# busyIdleDetectionStratasys.net
KiCad netlist of a schematic drawn in EAGLE
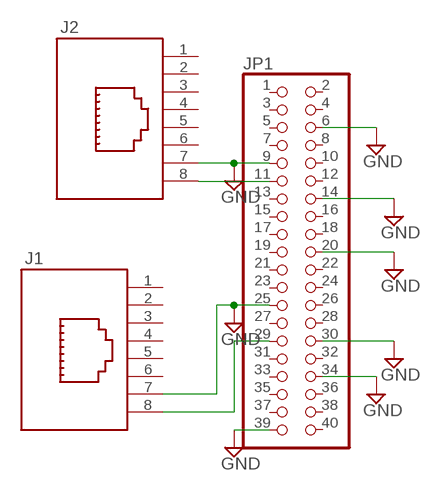
[diagram p0: schematic, sheet 1]

(export (version "E")
  (design (tool "Eeschema 10.0.6"))
  (components
    (comp (ref "J1")
      (value "634008137221")
      (footprint "eagle-import:634008137221")
      (libsource (lib "eagle-import") (part "634008137221"))
    )
    (comp (ref "J2")
      (value "634008137221")
      (footprint "eagle-import:634008137221")
      (libsource (lib "eagle-import") (part "634008137221"))
    )
    (comp (ref "JP1")
      (value "PINHD-2X20")
      (footprint "eagle-import:2X20")
      (libsource (lib "eagle-import") (part "PINHD-2X20"))
    )
  )
  (nets
    (net (code "1") (name "GND") (class "Default")
      (node (ref "J1") (pin "7") (pinfunction "2_7") (pintype "passive"))
      (node (ref "J2") (pin "7") (pinfunction "2_7") (pintype "passive"))
      (node (ref "JP1") (pin "14") (pinfunction "14_14") (pintype "passive"))
      (node (ref "JP1") (pin "20") (pinfunction "20_20") (pintype "passive"))
      (node (ref "JP1") (pin "25") (pinfunction "25_25") (pintype "passive"))
      (node (ref "JP1") (pin "30") (pinfunction "30_30") (pintype "passive"))
      (node (ref "JP1") (pin "34") (pinfunction "34_34") (pintype "passive"))
      (node (ref "JP1") (pin "39") (pinfunction "39_39") (pintype "passive"))
      (node (ref "JP1") (pin "6") (pinfunction "6_6") (pintype "passive"))
      (node (ref "JP1") (pin "9") (pinfunction "9_9") (pintype "passive"))
    )
    (net (code "2") (name "Net-(J1-1)") (class "Default")
      (node (ref "J1") (pin "8") (pinfunction "1_8") (pintype "passive"))
      (node (ref "JP1") (pin "29") (pinfunction "29_29") (pintype "passive"))
    )
    (net (code "3") (name "Net-(J2-1)") (class "Default")
      (node (ref "J2") (pin "8") (pinfunction "1_8") (pintype "passive"))
      (node (ref "JP1") (pin "11") (pinfunction "11_11") (pintype "passive"))
    )
    (net (code "4") (name "unconnected-(J1-3-Pad6)") (class "Default")
      (node (ref "J1") (pin "6") (pinfunction "3_6") (pintype "passive"))
    )
    (net (code "5") (name "unconnected-(J1-4-Pad5)") (class "Default")
      (node (ref "J1") (pin "5") (pinfunction "4_5") (pintype "passive"))
    )
    (net (code "6") (name "unconnected-(J1-5-Pad4)") (class "Default")
      (node (ref "J1") (pin "4") (pinfunction "5_4") (pintype "passive"))
    )
    (net (code "7") (name "unconnected-(J1-6-Pad3)") (class "Default")
      (node (ref "J1") (pin "3") (pinfunction "6_3") (pintype "passive"))
    )
    (net (code "8") (name "unconnected-(J1-7-Pad2)") (class "Default")
      (node (ref "J1") (pin "2") (pinfunction "7_2") (pintype "passive"))
    )
    (net (code "9") (name "unconnected-(J1-8-Pad1)") (class "Default")
      (node (ref "J1") (pin "1") (pinfunction "8_1") (pintype "passive"))
    )
    (net (code "10") (name "unconnected-(J2-3-Pad6)") (class "Default")
      (node (ref "J2") (pin "6") (pinfunction "3_6") (pintype "passive"))
    )
    (net (code "11") (name "unconnected-(J2-4-Pad5)") (class "Default")
      (node (ref "J2") (pin "5") (pinfunction "4_5") (pintype "passive"))
    )
    (net (code "12") (name "unconnected-(J2-5-Pad4)") (class "Default")
      (node (ref "J2") (pin "4") (pinfunction "5_4") (pintype "passive"))
    )
    (net (code "13") (name "unconnected-(J2-6-Pad3)") (class "Default")
      (node (ref "J2") (pin "3") (pinfunction "6_3") (pintype "passive"))
    )
    (net (code "14") (name "unconnected-(J2-7-Pad2)") (class "Default")
      (node (ref "J2") (pin "2") (pinfunction "7_2") (pintype "passive"))
    )
    (net (code "15") (name "unconnected-(J2-8-Pad1)") (class "Default")
      (node (ref "J2") (pin "1") (pinfunction "8_1") (pintype "passive"))
    )
    (net (code "16") (name "unconnected-(JP1-Pad1)") (class "Default")
      (node (ref "JP1") (pin "1") (pinfunction "1_1") (pintype "passive"))
    )
    (net (code "17") (name "unconnected-(JP1-Pad2)") (class "Default")
      (node (ref "JP1") (pin "2") (pinfunction "2_2") (pintype "passive"))
    )
    (net (code "18") (name "unconnected-(JP1-Pad3)") (class "Default")
      (node (ref "JP1") (pin "3") (pinfunction "3_3") (pintype "passive"))
    )
    (net (code "19") (name "unconnected-(JP1-Pad4)") (class "Default")
      (node (ref "JP1") (pin "4") (pinfunction "4_4") (pintype "passive"))
    )
    (net (code "20") (name "unconnected-(JP1-Pad5)") (class "Default")
      (node (ref "JP1") (pin "5") (pinfunction "5_5") (pintype "passive"))
    )
    (net (code "21") (name "unconnected-(JP1-Pad7)") (class "Default")
      (node (ref "JP1") (pin "7") (pinfunction "7_7") (pintype "passive"))
    )
    (net (code "22") (name "unconnected-(JP1-Pad8)") (class "Default")
      (node (ref "JP1") (pin "8") (pinfunction "8_8") (pintype "passive"))
    )
    (net (code "23") (name "unconnected-(JP1-Pad10)") (class "Default")
      (node (ref "JP1") (pin "10") (pinfunction "10_10") (pintype "passive"))
    )
    (net (code "24") (name "unconnected-(JP1-Pad12)") (class "Default")
      (node (ref "JP1") (pin "12") (pinfunction "12_12") (pintype "passive"))
    )
    (net (code "25") (name "unconnected-(JP1-Pad13)") (class "Default")
      (node (ref "JP1") (pin "13") (pinfunction "13_13") (pintype "passive"))
    )
    (net (code "26") (name "unconnected-(JP1-Pad15)") (class "Default")
      (node (ref "JP1") (pin "15") (pinfunction "15_15") (pintype "passive"))
    )
    (net (code "27") (name "unconnected-(JP1-Pad16)") (class "Default")
      (node (ref "JP1") (pin "16") (pinfunction "16_16") (pintype "passive"))
    )
    (net (code "28") (name "unconnected-(JP1-Pad17)") (class "Default")
      (node (ref "JP1") (pin "17") (pinfunction "17_17") (pintype "passive"))
    )
    (net (code "29") (name "unconnected-(JP1-Pad18)") (class "Default")
      (node (ref "JP1") (pin "18") (pinfunction "18_18") (pintype "passive"))
    )
    (net (code "30") (name "unconnected-(JP1-Pad19)") (class "Default")
      (node (ref "JP1") (pin "19") (pinfunction "19_19") (pintype "passive"))
    )
    (net (code "31") (name "unconnected-(JP1-Pad21)") (class "Default")
      (node (ref "JP1") (pin "21") (pinfunction "21_21") (pintype "passive"))
    )
    (net (code "32") (name "unconnected-(JP1-Pad22)") (class "Default")
      (node (ref "JP1") (pin "22") (pinfunction "22_22") (pintype "passive"))
    )
    (net (code "33") (name "unconnected-(JP1-Pad23)") (class "Default")
      (node (ref "JP1") (pin "23") (pinfunction "23_23") (pintype "passive"))
    )
    (net (code "34") (name "unconnected-(JP1-Pad24)") (class "Default")
      (node (ref "JP1") (pin "24") (pinfunction "24_24") (pintype "passive"))
    )
    (net (code "35") (name "unconnected-(JP1-Pad26)") (class "Default")
      (node (ref "JP1") (pin "26") (pinfunction "26_26") (pintype "passive"))
    )
    (net (code "36") (name "unconnected-(JP1-Pad27)") (class "Default")
      (node (ref "JP1") (pin "27") (pinfunction "27_27") (pintype "passive"))
    )
    (net (code "37") (name "unconnected-(JP1-Pad28)") (class "Default")
      (node (ref "JP1") (pin "28") (pinfunction "28_28") (pintype "passive"))
    )
    (net (code "38") (name "unconnected-(JP1-Pad31)") (class "Default")
      (node (ref "JP1") (pin "31") (pinfunction "31_31") (pintype "passive"))
    )
    (net (code "39") (name "unconnected-(JP1-Pad32)") (class "Default")
      (node (ref "JP1") (pin "32") (pinfunction "32_32") (pintype "passive"))
    )
    (net (code "40") (name "unconnected-(JP1-Pad33)") (class "Default")
      (node (ref "JP1") (pin "33") (pinfunction "33_33") (pintype "passive"))
    )
    (net (code "41") (name "unconnected-(JP1-Pad35)") (class "Default")
      (node (ref "JP1") (pin "35") (pinfunction "35_35") (pintype "passive"))
    )
    (net (code "42") (name "unconnected-(JP1-Pad36)") (class "Default")
      (node (ref "JP1") (pin "36") (pinfunction "36_36") (pintype "passive"))
    )
    (net (code "43") (name "unconnected-(JP1-Pad37)") (class "Default")
      (node (ref "JP1") (pin "37") (pinfunction "37_37") (pintype "passive"))
    )
    (net (code "44") (name "unconnected-(JP1-Pad38)") (class "Default")
      (node (ref "JP1") (pin "38") (pinfunction "38_38") (pintype "passive"))
    )
    (net (code "45") (name "unconnected-(JP1-Pad40)") (class "Default")
      (node (ref "JP1") (pin "40") (pinfunction "40_40") (pintype "passive"))
    )
  )
)
